# G8160-03-Sensor-Board-SCH_SH2__02.net
KiCad netlist of a schematic drawn in Altium Designer
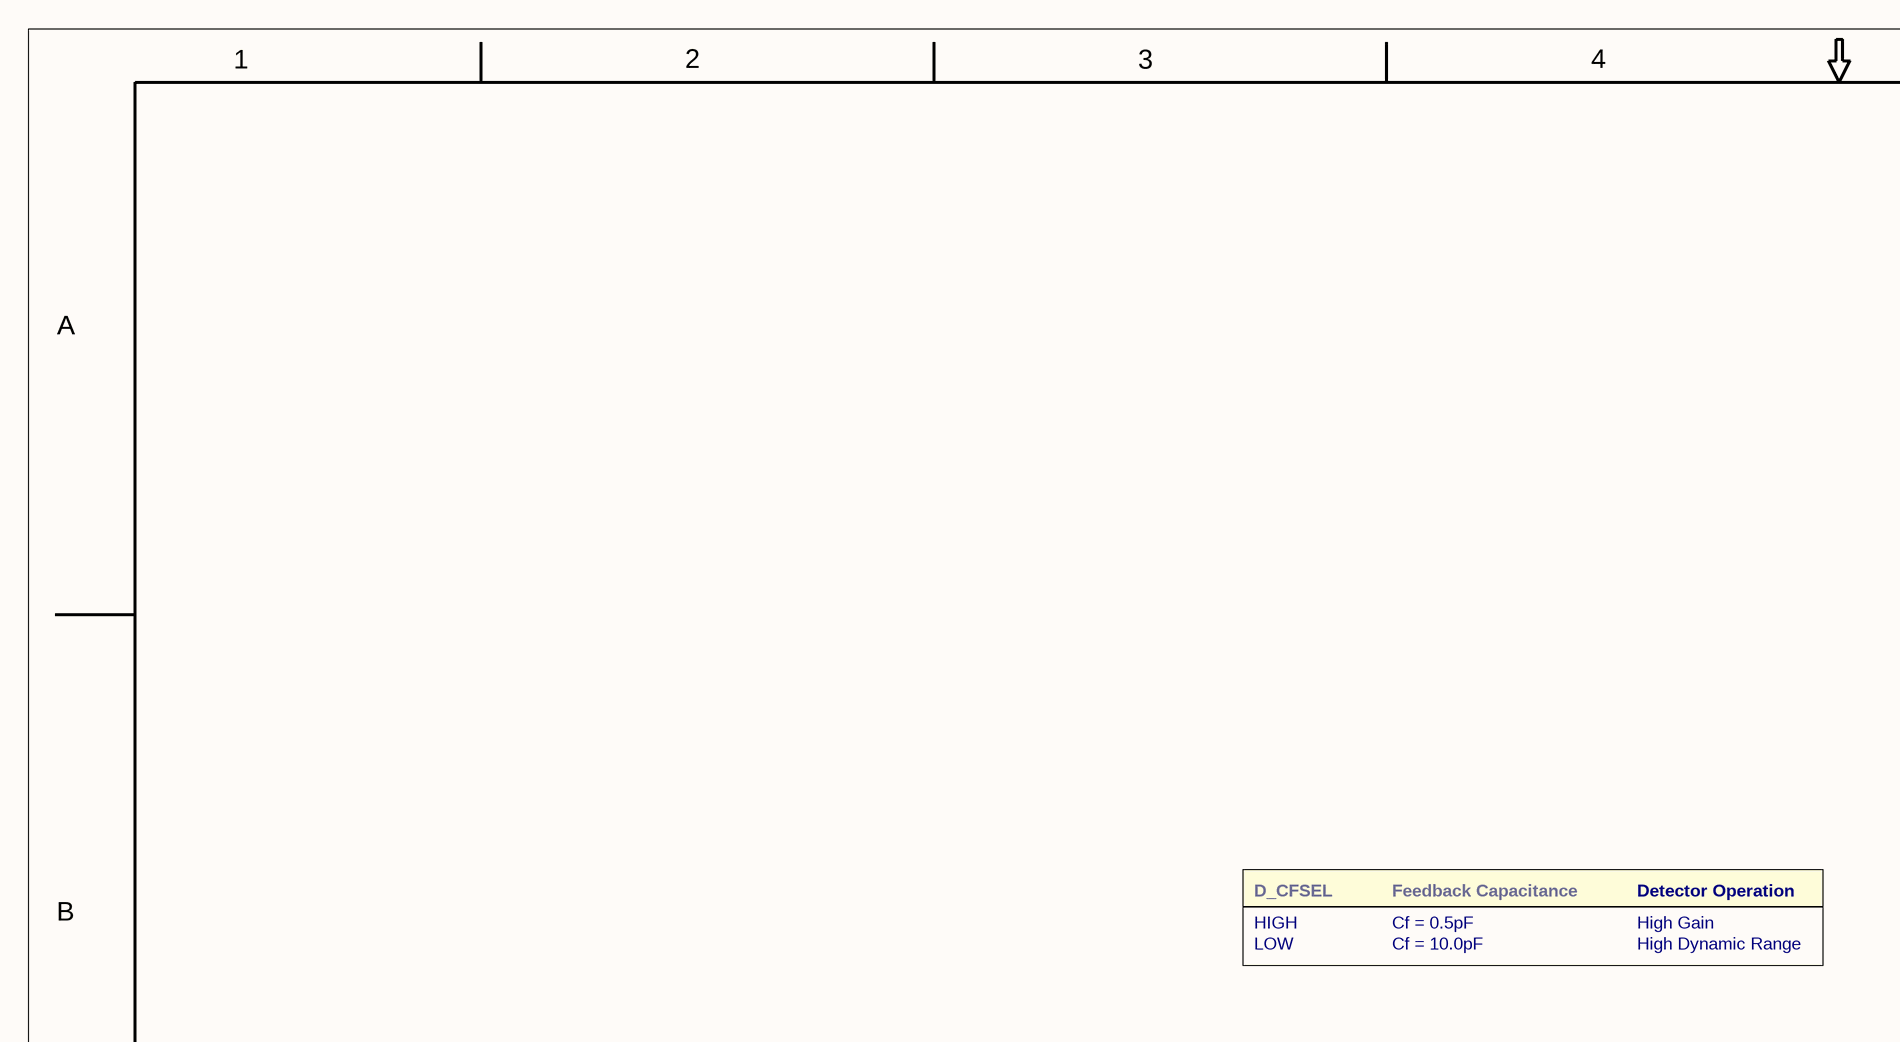
[diagram p0: G8160-03-Sensor-Board-SCH_SH2_(02).SchDoc, top left]
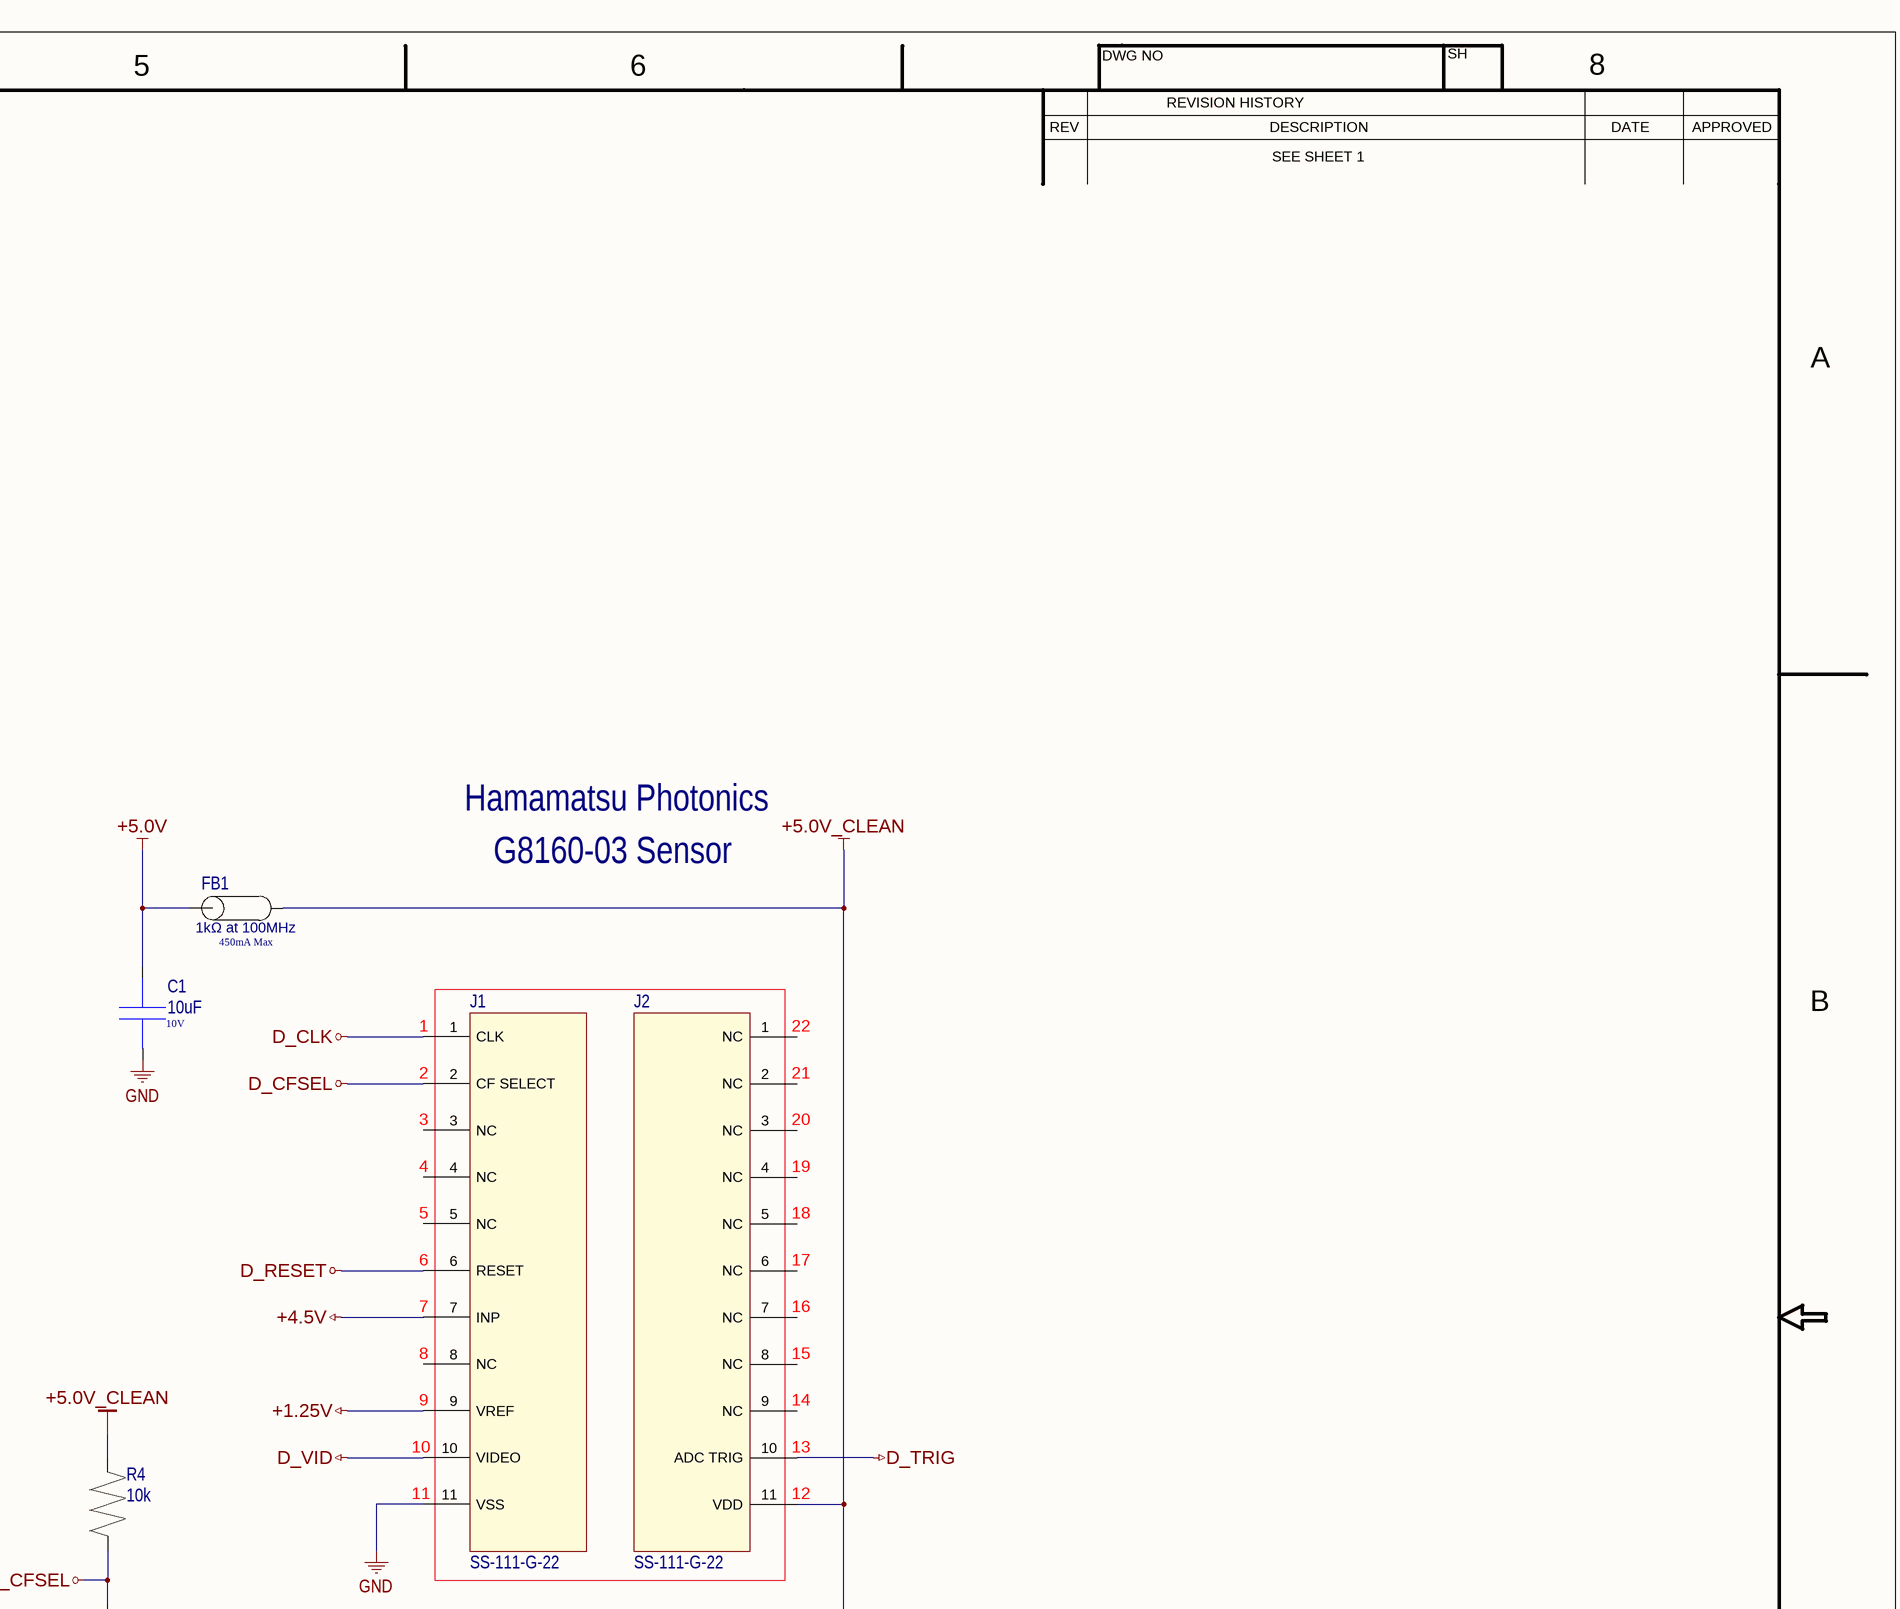
[diagram p1: G8160-03-Sensor-Board-SCH_SH2_(02).SchDoc, top right]
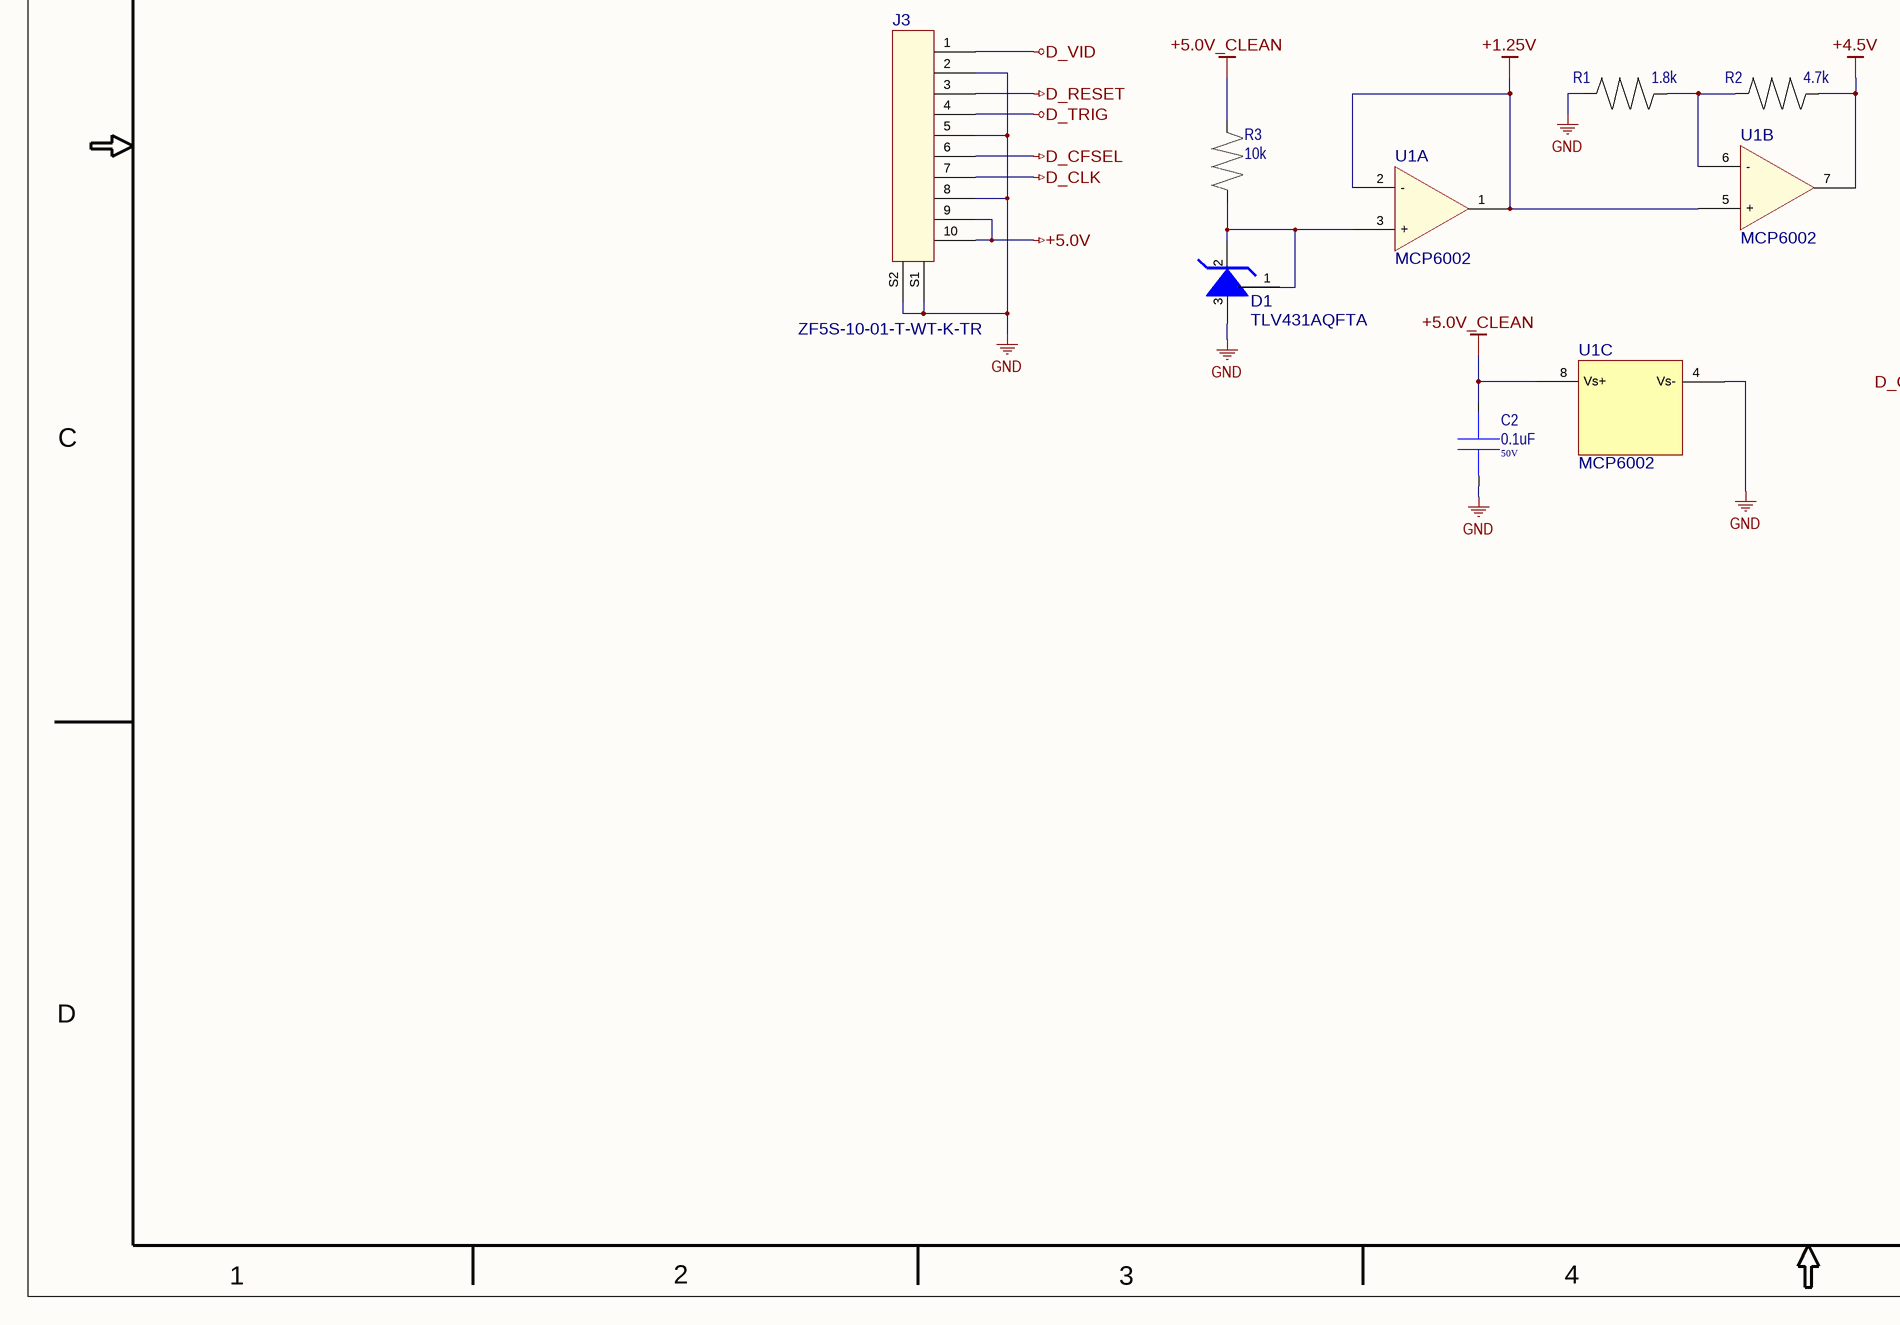
[diagram p2: G8160-03-Sensor-Board-SCH_SH2_(02).SchDoc, bottom left]
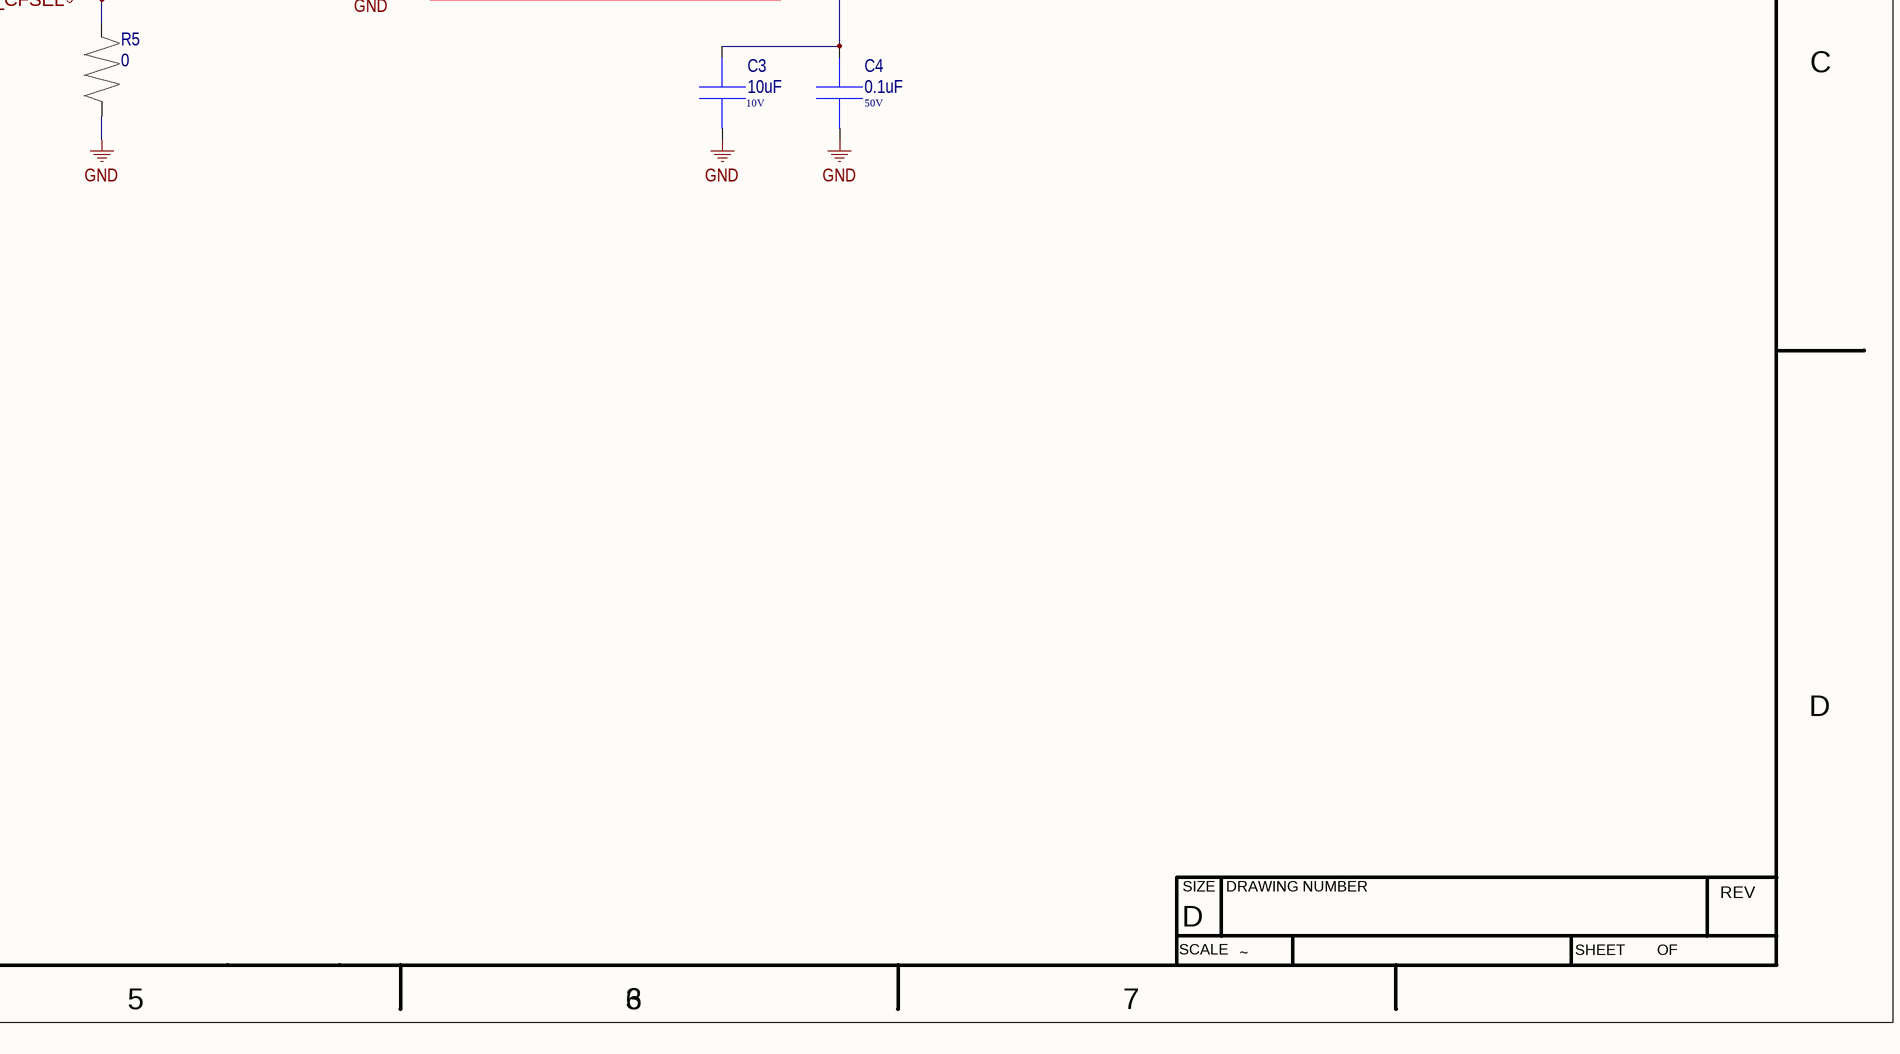
[diagram p3: G8160-03-Sensor-Board-SCH_SH2_(02).SchDoc, bottom right]

(export (version "E")
  (design (tool "Eeschema 10.0.6"))
  (components
    (comp (ref "C1")
      (value "10uF")
      (footprint "0402")
      (description "CAP CER 10UF 10V X6S 0603")
      (fields
        (field (name "PART NUMBER") "GRM188C81A106MA73D")
        (field (name "MANUFACTURER") "Murata Electronics")
        (field (name "VOLTAGE") "10V")
      )
      (libsource (lib "CAPACITORS") (part "CAP"))
    )
    (comp (ref "C2")
      (value "0.1uF")
      (footprint "0402")
      (description "CAP CER 0.1UF 50V X7R 0603")
      (fields
        (field (name "PART NUMBER") "C0603C104K5RAC3121")
        (field (name "MANUFACTURER") "KEMET")
        (field (name "VOLTAGE") "50V")
      )
      (libsource (lib "CAPACITORS") (part "CAP"))
    )
    (comp (ref "C3")
      (value "10uF")
      (footprint "0402")
      (description "CAP CER 10UF 10V X6S 0603")
      (fields
        (field (name "PART NUMBER") "GRM188C81A106MA73D")
        (field (name "MANUFACTURER") "Murata Electronics")
        (field (name "VOLTAGE") "10V")
      )
      (libsource (lib "CAPACITORS") (part "CAP"))
    )
    (comp (ref "C4")
      (value "0.1uF")
      (footprint "0402")
      (description "CAP CER 0.1UF 50V X7R 0603")
      (fields
        (field (name "PART NUMBER") "C0603C104K5RAC3121")
        (field (name "MANUFACTURER") "KEMET")
        (field (name "VOLTAGE") "50V")
      )
      (libsource (lib "CAPACITORS") (part "CAP"))
    )
    (comp (ref "D1")
      (value "TLV431AQFTA")
      (footprint "SOT-23-3")
      (description "Shunt Voltage Reference IC Adjustable 1.24V 18 VV ±1% 15 mA SOT-23-3")
      (fields (field (name "MANUFACTURER") "Diodes Incorporated"))
      (libsource (lib "TLV431AQFTA") (part "TLV431AQFTA"))
    )
    (comp (ref "FB1")
      (value "Ferrite_Bead")
      (footprint "0402")
      (description "Ferrite Beads 1000 OHM 25%")
      (fields
        (field (name "MANUFACTURER") "Murata Electronics")
        (field (name "PART NUMBER") "BLM18AG102SH1D")
        (field (name "RATED CURRENT") "450mA Max")
        (field (name "IMPEDANCE") "1kΩ at 100MHz")
      )
      (libsource (lib "Ferrite_Beads") (part "Ferrite_Bead"))
    )
    (comp (ref "J1")
      (value "SS-111-G-22")
      (footprint "SL-111-TT-11")
      (description "CONN RCPT .100\" 11POS TIN PCB")
      (fields (field (name "MANUFACTURER") "Samtec"))
      (libsource (lib "Connectors") (part "SL-111-TT-11"))
    )
    (comp (ref "J2")
      (value "SS-111-G-22")
      (footprint "SL-111-TT-11")
      (description "CONN RCPT .100\" 11POS TIN PCB")
      (fields (field (name "MANUFACTURER") "Samtec"))
      (libsource (lib "") (part "SL-111-TT-11_1"))
    )
    (comp (ref "J3")
      (value "ZF5S-10-01-T-WT-K-TR")
      (footprint "ZF5S-10-01-T-WT-K-TR")
      (fields (field (name "MANUFACTURER") "Samtec"))
      (libsource (lib "ZF5S-10-01-T-WT-K-TR") (part "ZF5S-10-01-T-WT-K-TR"))
    )
    (comp (ref "R1") (value "1.8k") (footprint "0402") (libsource (lib "RESISTORS") (part "RES")))
    (comp (ref "R2") (value "4.7k") (footprint "0402") (libsource (lib "RESISTORS") (part "RES")))
    (comp (ref "R3") (value "10k") (footprint "0402") (libsource (lib "RESISTORS") (part "RES")))
    (comp (ref "R4") (value "10k") (footprint "0402") (libsource (lib "RESISTORS") (part "RES")))
    (comp (ref "R5") (value "0") (footprint "0402") (libsource (lib "RESISTORS") (part "RES")))
    (comp (ref "U1")
      (value "MCP6002")
      (footprint "SOIC_8")
      (description "IC OPAMP VIDEO DUAL 8MSOP")
      (fields (field (name "PART NUMBER") "AD8072ARMZ") (field (name "MANUFACTURER") "Analog Devices Inc."))
      (libsource (lib "Op_Amps") (part "AD8072"))
    )
  )
  (nets
    (net (code "1") (name "+1.25V") (class "Default")
      (node (ref "J1") (pin "9") (pinfunction "VREF_9") (pintype "passive"))
      (node (ref "U1") (pin "1") (pinfunction "OUT_1") (pintype "passive"))
      (node (ref "U1") (pin "2") (pinfunction "-_2") (pintype "passive"))
      (node (ref "U1") (pin "5") (pinfunction "+_5") (pintype "passive"))
    )
    (net (code "2") (name "+4.5V") (class "Default")
      (node (ref "J1") (pin "7") (pinfunction "INP_7") (pintype "passive"))
      (node (ref "R2") (pin "1") (pinfunction "1_1") (pintype "passive"))
      (node (ref "U1") (pin "7") (pinfunction "OUT_7") (pintype "passive"))
    )
    (net (code "3") (name "+5.0V") (class "Default")
      (node (ref "C1") (pin "2") (pinfunction "2_2") (pintype "passive"))
      (node (ref "FB1") (pin "1") (pinfunction "1_1") (pintype "passive"))
      (node (ref "J3") (pin "10") (pinfunction "10_10") (pintype "passive"))
      (node (ref "J3") (pin "9") (pinfunction "9_9") (pintype "passive"))
    )
    (net (code "4") (name "+5.0V_CLEAN") (class "Default")
      (node (ref "C2") (pin "2") (pinfunction "2_2") (pintype "passive"))
      (node (ref "C3") (pin "2") (pinfunction "2_2") (pintype "passive"))
      (node (ref "C4") (pin "2") (pinfunction "2_2") (pintype "passive"))
      (node (ref "FB1") (pin "2") (pinfunction "2_2") (pintype "passive"))
      (node (ref "J2") (pin "11") (pinfunction "VDD_11") (pintype "passive"))
      (node (ref "R3") (pin "2") (pinfunction "2_2") (pintype "passive"))
      (node (ref "R4") (pin "2") (pinfunction "2_2") (pintype "passive"))
      (node (ref "U1") (pin "8") (pinfunction "Vs+_8") (pintype "power_in"))
    )
    (net (code "5") (name "D_CFSEL") (class "Default")
      (node (ref "J1") (pin "2") (pinfunction "CF_SELECT_2") (pintype "passive"))
      (node (ref "J3") (pin "6") (pinfunction "6_6") (pintype "passive"))
      (node (ref "R4") (pin "1") (pinfunction "1_1") (pintype "passive"))
      (node (ref "R5") (pin "2") (pinfunction "2_2") (pintype "passive"))
    )
    (net (code "6") (name "D_CLK") (class "Default")
      (node (ref "J1") (pin "1") (pinfunction "CLK_1") (pintype "passive"))
      (node (ref "J3") (pin "7") (pinfunction "7_7") (pintype "passive"))
    )
    (net (code "7") (name "D_RESET") (class "Default")
      (node (ref "J1") (pin "6") (pinfunction "RESET_6") (pintype "passive"))
      (node (ref "J3") (pin "3") (pinfunction "3_3") (pintype "passive"))
    )
    (net (code "8") (name "D_TRIG") (class "Default")
      (node (ref "J2") (pin "10") (pinfunction "ADC_TRIG_10") (pintype "passive"))
      (node (ref "J3") (pin "4") (pinfunction "4_4") (pintype "passive"))
    )
    (net (code "9") (name "D_VID") (class "Default")
      (node (ref "J1") (pin "10") (pinfunction "VIDEO_10") (pintype "passive"))
      (node (ref "J3") (pin "1") (pinfunction "1_1") (pintype "passive"))
    )
    (net (code "10") (name "GND") (class "Default")
      (node (ref "C1") (pin "1") (pinfunction "1_1") (pintype "passive"))
      (node (ref "C2") (pin "1") (pinfunction "1_1") (pintype "passive"))
      (node (ref "C3") (pin "1") (pinfunction "1_1") (pintype "passive"))
      (node (ref "C4") (pin "1") (pinfunction "1_1") (pintype "passive"))
      (node (ref "D1") (pin "3") (pinfunction "A_3") (pintype "passive"))
      (node (ref "J1") (pin "11") (pinfunction "VSS_11") (pintype "passive"))
      (node (ref "J3") (pin "2") (pinfunction "2_2") (pintype "passive"))
      (node (ref "J3") (pin "5") (pinfunction "5_5") (pintype "passive"))
      (node (ref "J3") (pin "8") (pinfunction "8_8") (pintype "passive"))
      (node (ref "J3") (pin "S1") (pinfunction "S1_S1") (pintype "passive"))
      (node (ref "J3") (pin "S2") (pinfunction "S2_S2") (pintype "passive"))
      (node (ref "R1") (pin "2") (pinfunction "2_2") (pintype "passive"))
      (node (ref "R5") (pin "1") (pinfunction "1_1") (pintype "passive"))
      (node (ref "U1") (pin "4") (pinfunction "Vs-_4") (pintype "power_in"))
    )
    (net (code "11") (name "Net-(D1-K)") (class "Default")
      (node (ref "D1") (pin "1") (pinfunction "REF_1") (pintype "power_in"))
      (node (ref "D1") (pin "2") (pinfunction "K_2") (pintype "passive"))
      (node (ref "R3") (pin "1") (pinfunction "1_1") (pintype "passive"))
      (node (ref "U1") (pin "3") (pinfunction "+_3") (pintype "passive"))
    )
    (net (code "12") (name "Net-(U1B--)") (class "Default")
      (node (ref "R1") (pin "1") (pinfunction "1_1") (pintype "passive"))
      (node (ref "R2") (pin "2") (pinfunction "2_2") (pintype "passive"))
      (node (ref "U1") (pin "6") (pinfunction "-_6") (pintype "passive"))
    )
    (net (code "13") (name "unconnected-(J1-NC-Pad3)") (class "Default")
      (node (ref "J1") (pin "3") (pinfunction "NC_3") (pintype "passive"))
    )
    (net (code "14") (name "unconnected-(J1-NC-Pad4)") (class "Default")
      (node (ref "J1") (pin "4") (pinfunction "NC_4") (pintype "passive"))
    )
    (net (code "15") (name "unconnected-(J1-NC-Pad5)") (class "Default")
      (node (ref "J1") (pin "5") (pinfunction "NC_5") (pintype "passive"))
    )
    (net (code "16") (name "unconnected-(J1-NC-Pad8)") (class "Default")
      (node (ref "J1") (pin "8") (pinfunction "NC_8") (pintype "passive"))
    )
    (net (code "17") (name "unconnected-(J2-NC-Pad1)") (class "Default")
      (node (ref "J2") (pin "1") (pinfunction "NC_1") (pintype "passive"))
    )
    (net (code "18") (name "unconnected-(J2-NC-Pad2)") (class "Default")
      (node (ref "J2") (pin "2") (pinfunction "NC_2") (pintype "passive"))
    )
    (net (code "19") (name "unconnected-(J2-NC-Pad3)") (class "Default")
      (node (ref "J2") (pin "3") (pinfunction "NC_3") (pintype "passive"))
    )
    (net (code "20") (name "unconnected-(J2-NC-Pad4)") (class "Default")
      (node (ref "J2") (pin "4") (pinfunction "NC_4") (pintype "passive"))
    )
    (net (code "21") (name "unconnected-(J2-NC-Pad5)") (class "Default")
      (node (ref "J2") (pin "5") (pinfunction "NC_5") (pintype "passive"))
    )
    (net (code "22") (name "unconnected-(J2-NC-Pad6)") (class "Default")
      (node (ref "J2") (pin "6") (pinfunction "NC_6") (pintype "passive"))
    )
    (net (code "23") (name "unconnected-(J2-NC-Pad7)") (class "Default")
      (node (ref "J2") (pin "7") (pinfunction "NC_7") (pintype "passive"))
    )
    (net (code "24") (name "unconnected-(J2-NC-Pad8)") (class "Default")
      (node (ref "J2") (pin "8") (pinfunction "NC_8") (pintype "passive"))
    )
    (net (code "25") (name "unconnected-(J2-NC-Pad9)") (class "Default")
      (node (ref "J2") (pin "9") (pinfunction "NC_9") (pintype "passive"))
    )
  )
)
